# MG_0428.net
KiCad netlist of a schematic drawn in EasyEDA Pro
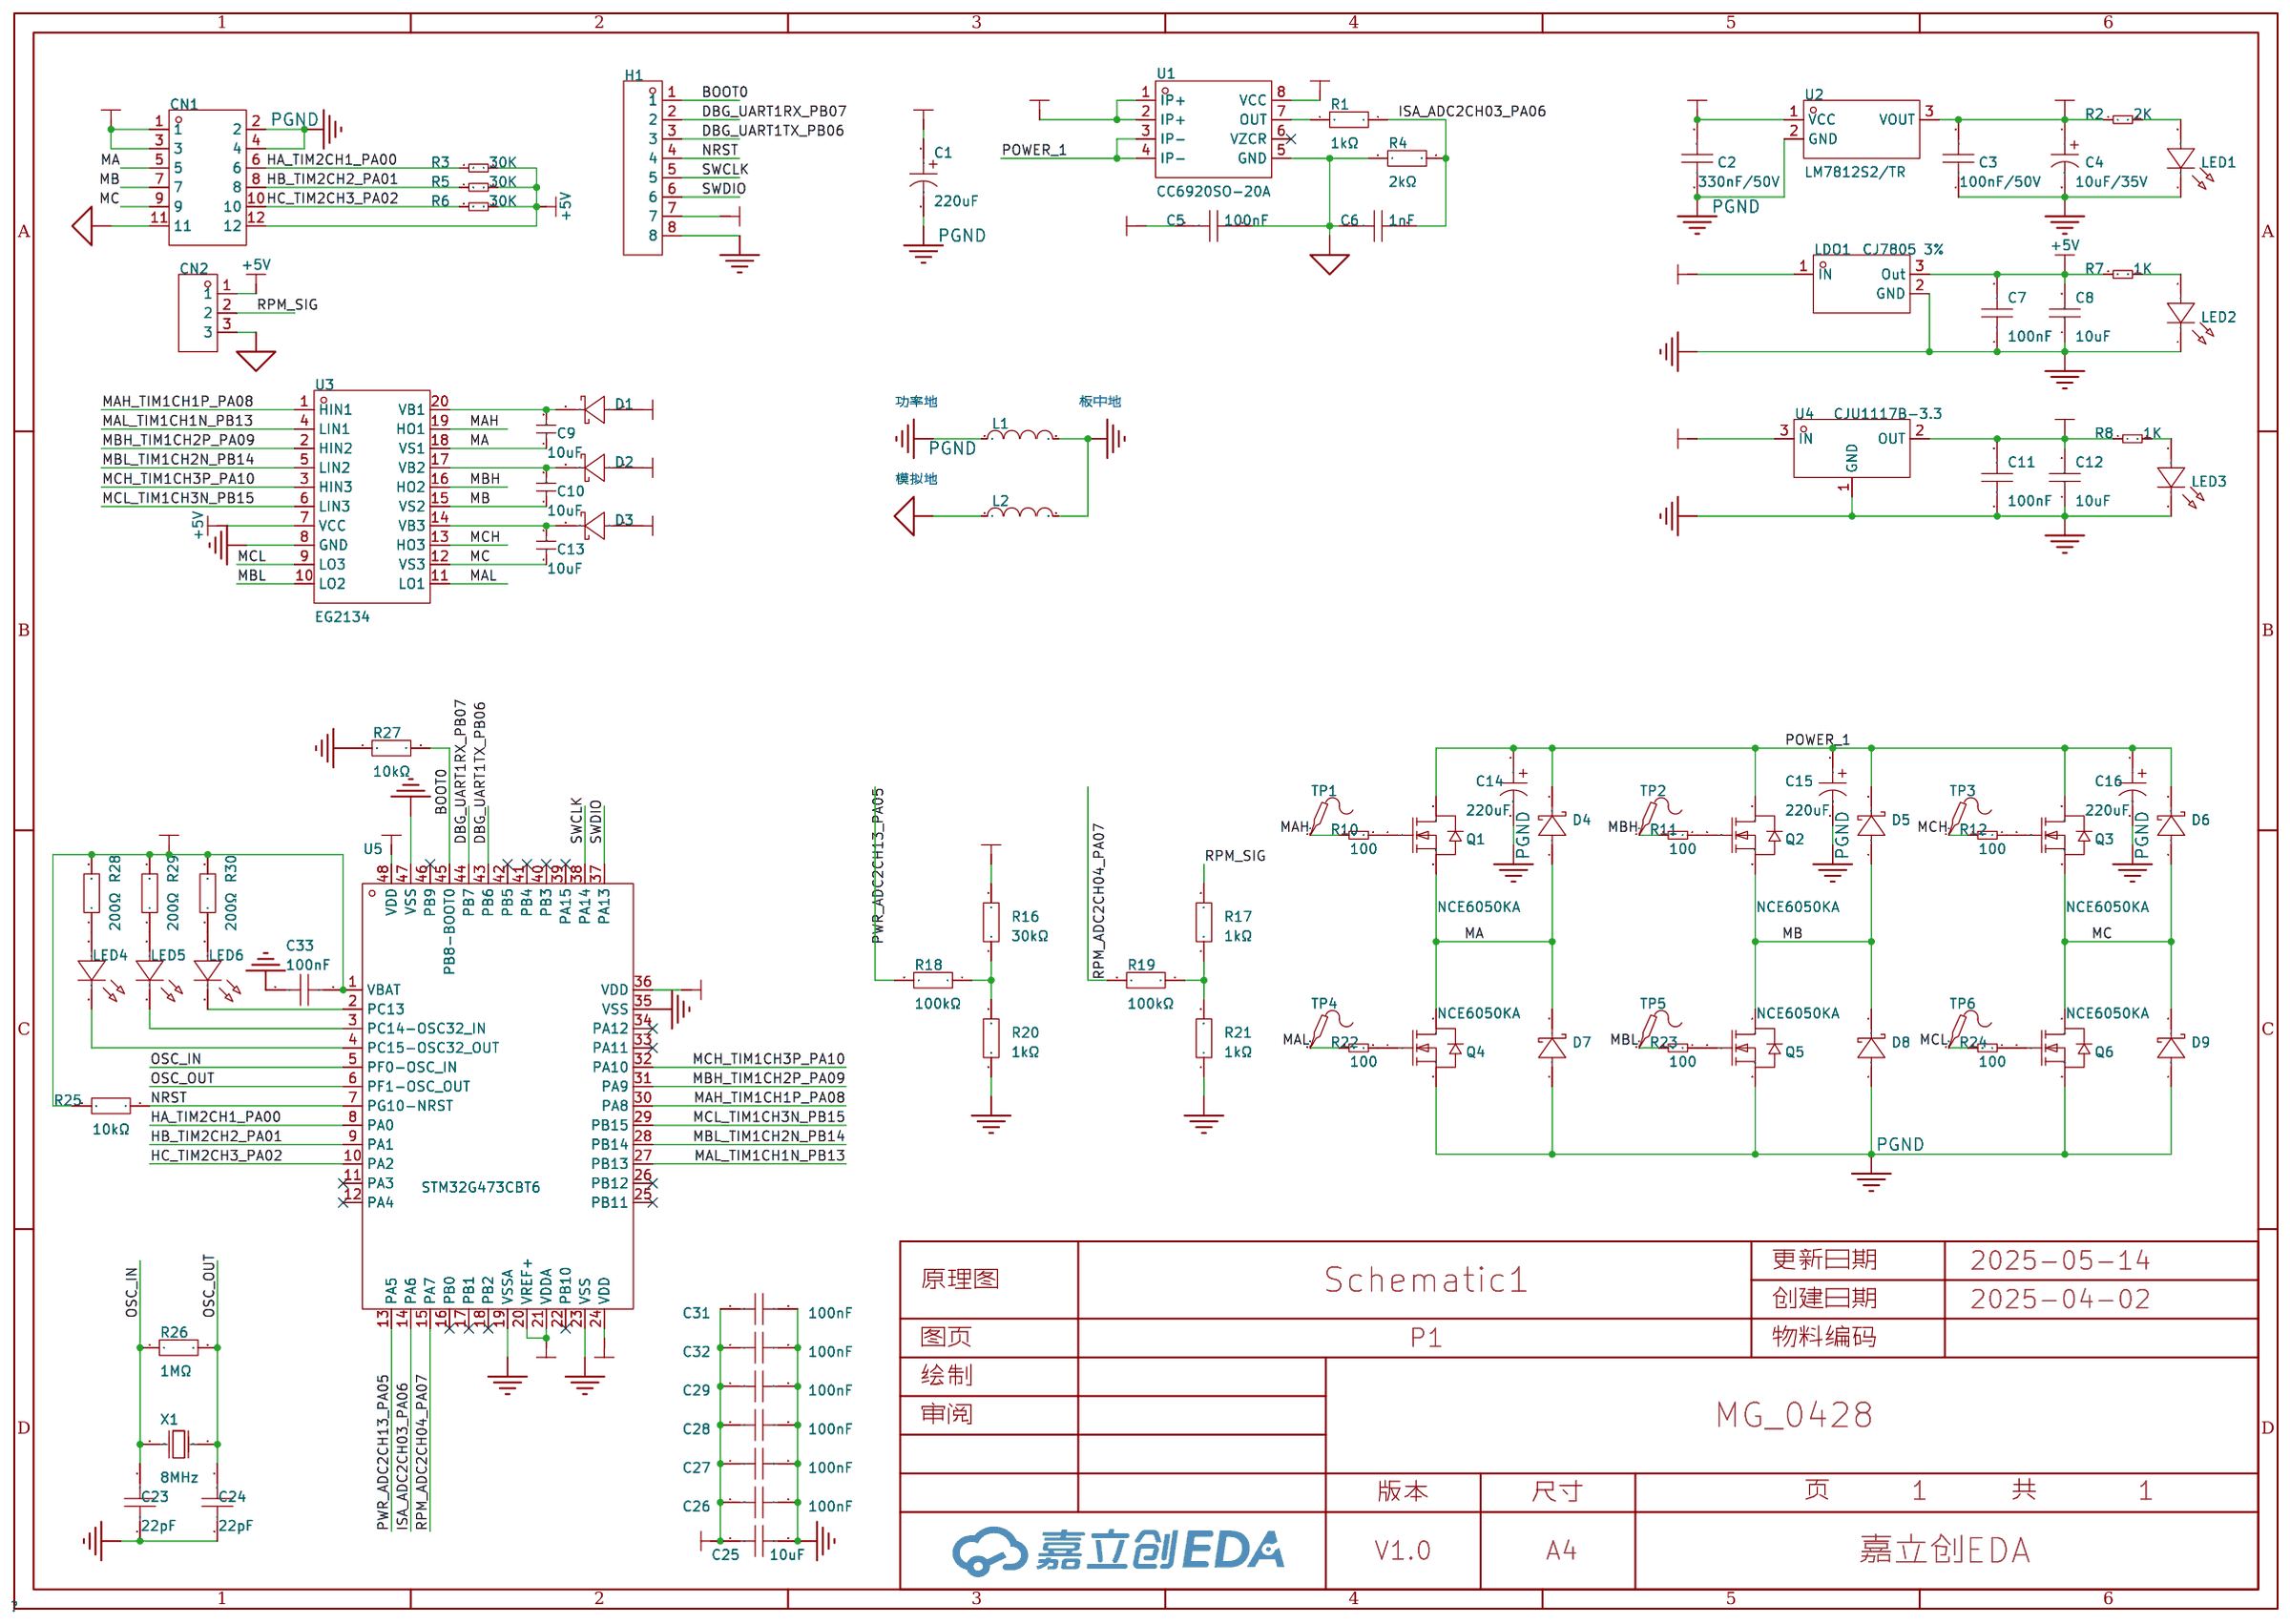
[diagram p0: schematic sheet]

(export (version "E")
  (design (tool "Eeschema 10.0.6"))
  (components
    (comp (ref "C1")
      (value "220uF")
      (footprint "easyedapro:CAP-SMD_BD10.0-L10.3-W10.3-LS11.0-FD")
      (description "容值:220uF;精度:±20%;额定电压:50V;纹波电流:230mA@120Hz;等效串联电阻:-;")
      (fields
        (field (name "Manufacturer Part") "RVT220UF50V67RV0021")
        (field (name "Manufacturer") "KNSCHA(科尼盛)")
      )
      (libsource (lib "easyedapro") (part "RVT220UF50V67RV0021"))
    )
    (comp (ref "C2")
      (value "330nF/50V")
      (footprint "easyedapro:C0603")
      (description "容值:330nF;精度:±10%;额定电压:50V;材质(温度系数):X7R;")
      (fields
        (field (name "Manufacturer Part") "TCC0603X7R334K500CT")
        (field (name "Manufacturer") "CCTC(三环)")
      )
      (libsource (lib "easyedapro") (part "TCC0603X7R334K500CT"))
    )
    (comp (ref "C3")
      (value "100nF/50V")
      (footprint "easyedapro:C0603")
      (description "容值:100nF;精度:±10%;额定电压:50V;材质(温度系数):X7R;")
      (fields
        (field (name "Manufacturer Part") "CC0603KRX7R9BB104")
        (field (name "Manufacturer") "YAGEO(国巨)")
      )
      (libsource (lib "easyedapro") (part "CC0603KRX7R9BB104"))
    )
    (comp (ref "C4")
      (value "10uF/35V")
      (footprint "easyedapro:CAP-SMD_BD6.3-L6.6-W6.6-LS7.4-FD")
      (description "容值:220uF;精度:±20%;额定电压:25V;纹波电流:150mA@120Hz;等效串联电阻:-;")
      (fields (field (name "Manufacturer Part") "RVT1E221M0607") (field (name "Manufacturer") "ROQANG(容强)"))
      (libsource (lib "easyedapro") (part "RVT1E221M0607_C2918361"))
    )
    (comp (ref "C5")
      (value "100nF")
      (footprint "easyedapro:C0603")
      (description "容值:100nF;精度:±10%;额定电压:50V;材质(温度系数):X7R;")
      (fields
        (field (name "Manufacturer Part") "CC0603KRX7R9BB104")
        (field (name "Manufacturer") "YAGEO(国巨)")
      )
      (libsource (lib "easyedapro") (part "CC0603KRX7R9BB104"))
    )
    (comp (ref "C6")
      (value "1nF")
      (footprint "easyedapro:C0603")
      (description "容值:100nF;精度:±10%;额定电压:50V;材质(温度系数):X7R;")
      (fields
        (field (name "Manufacturer Part") "CC0603KRX7R9BB104")
        (field (name "Manufacturer") "YAGEO(国巨)")
      )
      (libsource (lib "easyedapro") (part "CC0603KRX7R9BB104"))
    )
    (comp (ref "C7")
      (value "100nF")
      (footprint "easyedapro:C0603")
      (description "容值:100nF;精度:±10%;额定电压:50V;材质(温度系数):X7R;")
      (fields
        (field (name "Manufacturer Part") "CC0603KRX7R9BB104")
        (field (name "Manufacturer") "YAGEO(国巨)")
      )
      (libsource (lib "easyedapro") (part "CC0603KRX7R9BB104"))
    )
    (comp (ref "C8")
      (value "10uF")
      (footprint "easyedapro:C1206")
      (description "容值:10uF;精度:±10%;额定电压:50V;材质(温度系数):X5R;")
      (fields
        (field (name "Manufacturer Part") "CL31A106KBHNNNE")
        (field (name "Manufacturer") "SAMSUNG(三星)")
      )
      (libsource (lib "easyedapro") (part "CL31A106KBHNNNE"))
    )
    (comp (ref "C9")
      (value "10uF")
      (footprint "easyedapro:C0603")
      (libsource (lib "easyedapro") (part "CapAcitance"))
    )
    (comp (ref "C10")
      (value "10uF")
      (footprint "easyedapro:C0603")
      (libsource (lib "easyedapro") (part "CapAcitance"))
    )
    (comp (ref "C11")
      (value "100nF")
      (footprint "easyedapro:C0603")
      (description "容值:100nF;精度:±10%;额定电压:50V;材质(温度系数):X7R;")
      (fields
        (field (name "Manufacturer Part") "CC0603KRX7R9BB104")
        (field (name "Manufacturer") "YAGEO(国巨)")
      )
      (libsource (lib "easyedapro") (part "CC0603KRX7R9BB104"))
    )
    (comp (ref "C12")
      (value "10uF")
      (footprint "easyedapro:C1206")
      (description "容值:10uF;精度:±10%;额定电压:50V;材质(温度系数):X5R;")
      (fields
        (field (name "Manufacturer Part") "CL31A106KBHNNNE")
        (field (name "Manufacturer") "SAMSUNG(三星)")
      )
      (libsource (lib "easyedapro") (part "CL31A106KBHNNNE"))
    )
    (comp (ref "C13")
      (value "10uF")
      (footprint "easyedapro:C0603")
      (libsource (lib "easyedapro") (part "CapAcitance"))
    )
    (comp (ref "C14")
      (value "220uF")
      (footprint "easyedapro:CAP-SMD_BD6.3-L6.6-W6.6-LS7.4-FD")
      (description "容值:220uF;精度:±20%;额定电压:25V;纹波电流:150mA@120Hz;等效串联电阻:-;")
      (fields (field (name "Manufacturer Part") "RVT1E221M0607") (field (name "Manufacturer") "ROQANG(容强)"))
      (libsource (lib "easyedapro") (part "RVT1E221M0607_C2918361"))
    )
    (comp (ref "C15")
      (value "220uF")
      (footprint "easyedapro:CAP-SMD_BD6.3-L6.6-W6.6-LS7.4-FD")
      (description "容值:220uF;精度:±20%;额定电压:25V;纹波电流:150mA@120Hz;等效串联电阻:-;")
      (fields (field (name "Manufacturer Part") "RVT1E221M0607") (field (name "Manufacturer") "ROQANG(容强)"))
      (libsource (lib "easyedapro") (part "RVT1E221M0607_C2918361"))
    )
    (comp (ref "C16")
      (value "220uF")
      (footprint "easyedapro:CAP-SMD_BD6.3-L6.6-W6.6-LS7.4-FD")
      (description "容值:220uF;精度:±20%;额定电压:25V;纹波电流:150mA@120Hz;等效串联电阻:-;")
      (fields (field (name "Manufacturer Part") "RVT1E221M0607") (field (name "Manufacturer") "ROQANG(容强)"))
      (libsource (lib "easyedapro") (part "RVT1E221M0607_C2918361"))
    )
    (comp (ref "C23")
      (value "22pF")
      (footprint "easyedapro:C0402")
      (description "容值:22pF;精度:±1%;额定电压:50V;材质(温度系数):NP0;")
      (fields
        (field (name "Manufacturer Part") "CC0402FRNPO9BN220")
        (field (name "Manufacturer") "YAGEO(国巨)")
      )
      (libsource (lib "easyedapro") (part "CC0402FRNPO9BN220"))
    )
    (comp (ref "C24")
      (value "22pF")
      (footprint "easyedapro:C0402")
      (description "容值:22pF;精度:±1%;额定电压:50V;材质(温度系数):NP0;")
      (fields
        (field (name "Manufacturer Part") "CC0402FRNPO9BN220")
        (field (name "Manufacturer") "YAGEO(国巨)")
      )
      (libsource (lib "easyedapro") (part "CC0402FRNPO9BN220"))
    )
    (comp (ref "C25")
      (value "10uF")
      (footprint "easyedapro:C0402")
      (description "容值:10uF;精度:±20%;额定电压:10V;材质(温度系数):X5R;")
      (fields
        (field (name "Manufacturer Part") "HGC0402R5106M100NTEJ")
        (field (name "Manufacturer") "Chinocera(华瓷)")
      )
      (libsource (lib "easyedapro") (part "HGC0402R5106M100NTEJ"))
    )
    (comp (ref "C26")
      (value "100nF")
      (footprint "easyedapro:C0402")
      (description "容值:100nF;精度:±10%;额定电压:50V;材质(温度系数):X7R;")
      (fields
        (field (name "Manufacturer Part") "CL05B104KB54PNC")
        (field (name "Manufacturer") "SAMSUNG(三星)")
      )
      (libsource (lib "easyedapro") (part "CL05B104KB54PNC"))
    )
    (comp (ref "C27")
      (value "100nF")
      (footprint "easyedapro:C0402")
      (description "容值:100nF;精度:±10%;额定电压:50V;材质(温度系数):X7R;")
      (fields
        (field (name "Manufacturer Part") "CL05B104KB54PNC")
        (field (name "Manufacturer") "SAMSUNG(三星)")
      )
      (libsource (lib "easyedapro") (part "CL05B104KB54PNC"))
    )
    (comp (ref "C28")
      (value "100nF")
      (footprint "easyedapro:C0402")
      (description "容值:100nF;精度:±10%;额定电压:50V;材质(温度系数):X7R;")
      (fields
        (field (name "Manufacturer Part") "CL05B104KB54PNC")
        (field (name "Manufacturer") "SAMSUNG(三星)")
      )
      (libsource (lib "easyedapro") (part "CL05B104KB54PNC"))
    )
    (comp (ref "C29")
      (value "100nF")
      (footprint "easyedapro:C0402")
      (description "容值:100nF;精度:±10%;额定电压:50V;材质(温度系数):X7R;")
      (fields
        (field (name "Manufacturer Part") "CL05B104KB54PNC")
        (field (name "Manufacturer") "SAMSUNG(三星)")
      )
      (libsource (lib "easyedapro") (part "CL05B104KB54PNC"))
    )
    (comp (ref "C31")
      (value "100nF")
      (footprint "easyedapro:C0402")
      (description "容值:100nF;精度:±10%;额定电压:50V;材质(温度系数):X7R;")
      (fields
        (field (name "Manufacturer Part") "CL05B104KB54PNC")
        (field (name "Manufacturer") "SAMSUNG(三星)")
      )
      (libsource (lib "easyedapro") (part "CL05B104KB54PNC"))
    )
    (comp (ref "C32")
      (value "100nF")
      (footprint "easyedapro:C0402")
      (description "容值:100nF;精度:±10%;额定电压:50V;材质(温度系数):X7R;")
      (fields
        (field (name "Manufacturer Part") "CL05B104KB54PNC")
        (field (name "Manufacturer") "SAMSUNG(三星)")
      )
      (libsource (lib "easyedapro") (part "CL05B104KB54PNC"))
    )
    (comp (ref "C33")
      (value "100nF")
      (footprint "easyedapro:C0402")
      (description "容值:100nF;精度:±10%;额定电压:50V;材质(温度系数):X7R;")
      (fields
        (field (name "Manufacturer Part") "CL05B104KB54PNC")
        (field (name "Manufacturer") "SAMSUNG(三星)")
      )
      (libsource (lib "easyedapro") (part "CL05B104KB54PNC"))
    )
    (comp (ref "CN1")
      (value "HC-MX3.0-2*6A")
      (footprint "easyedapro:CONN-TH_12P-P3.00_HC-MX3.0-2X6A")
      (fields (field (name "Manufacturer") "HCTL(华灿天禄)"))
      (libsource (lib "easyedapro") (part "HC-MX3.0-2*6A"))
    )
    (comp (ref "CN2")
      (value "ZX-XH2.54-3PZZ")
      (footprint "easyedapro:CONN-TH_3P-P2.54_2501S-3P")
      (fields (field (name "Manufacturer") "Megastar(兆星)"))
      (libsource (lib "easyedapro") (part "ZX-XH2.54-3PZZ"))
    )
    (comp (ref "D1")
      (value "BAT46W")
      (footprint "easyedapro:SOD-123_L2.7-W1.6-LS3.7-FD")
      (description "二极管配置:独立式;正向压降(Vf):450mV@10mA;直流反向耐压(Vr):100V;整流电流:150mA;")
      (fields (field (name "Manufacturer") "宏迦橙"))
      (libsource (lib "easyedapro") (part "BAT46W_C7420332"))
    )
    (comp (ref "D2")
      (value "BAT46W")
      (footprint "easyedapro:SOD-123_L2.7-W1.6-LS3.7-FD")
      (description "二极管配置:独立式;正向压降(Vf):450mV@10mA;直流反向耐压(Vr):100V;整流电流:150mA;")
      (fields (field (name "Manufacturer") "宏迦橙"))
      (libsource (lib "easyedapro") (part "BAT46W_C7420332"))
    )
    (comp (ref "D3")
      (value "BAT46W")
      (footprint "easyedapro:SOD-123_L2.7-W1.6-LS3.7-FD")
      (description "二极管配置:独立式;正向压降(Vf):450mV@10mA;直流反向耐压(Vr):100V;整流电流:150mA;")
      (fields (field (name "Manufacturer") "宏迦橙"))
      (libsource (lib "easyedapro") (part "BAT46W_C7420332"))
    )
    (comp (ref "D4")
      (value "BAT46W")
      (footprint "easyedapro:SOD-123_L2.7-W1.6-LS3.7-FD")
      (description "二极管配置:独立式;正向压降(Vf):450mV@10mA;直流反向耐压(Vr):100V;整流电流:150mA;")
      (fields (field (name "Manufacturer") "宏迦橙"))
      (libsource (lib "easyedapro") (part "BAT46W_C7420332"))
    )
    (comp (ref "D5")
      (value "BAT46W")
      (footprint "easyedapro:SOD-123_L2.7-W1.6-LS3.7-FD")
      (description "二极管配置:独立式;正向压降(Vf):450mV@10mA;直流反向耐压(Vr):100V;整流电流:150mA;")
      (fields (field (name "Manufacturer") "宏迦橙"))
      (libsource (lib "easyedapro") (part "BAT46W_C7420332"))
    )
    (comp (ref "D6")
      (value "BAT46W")
      (footprint "easyedapro:SOD-123_L2.7-W1.6-LS3.7-FD")
      (description "二极管配置:独立式;正向压降(Vf):450mV@10mA;直流反向耐压(Vr):100V;整流电流:150mA;")
      (fields (field (name "Manufacturer") "宏迦橙"))
      (libsource (lib "easyedapro") (part "BAT46W_C7420332"))
    )
    (comp (ref "D7")
      (value "BAT46W")
      (footprint "easyedapro:SOD-123_L2.7-W1.6-LS3.7-FD")
      (description "二极管配置:独立式;正向压降(Vf):450mV@10mA;直流反向耐压(Vr):100V;整流电流:150mA;")
      (fields (field (name "Manufacturer") "宏迦橙"))
      (libsource (lib "easyedapro") (part "BAT46W_C7420332"))
    )
    (comp (ref "D8")
      (value "BAT46W")
      (footprint "easyedapro:SOD-123_L2.7-W1.6-LS3.7-FD")
      (description "二极管配置:独立式;正向压降(Vf):450mV@10mA;直流反向耐压(Vr):100V;整流电流:150mA;")
      (fields (field (name "Manufacturer") "宏迦橙"))
      (libsource (lib "easyedapro") (part "BAT46W_C7420332"))
    )
    (comp (ref "D9")
      (value "BAT46W")
      (footprint "easyedapro:SOD-123_L2.7-W1.6-LS3.7-FD")
      (description "二极管配置:独立式;正向压降(Vf):450mV@10mA;直流反向耐压(Vr):100V;整流电流:150mA;")
      (fields (field (name "Manufacturer") "宏迦橙"))
      (libsource (lib "easyedapro") (part "BAT46W_C7420332"))
    )
    (comp (ref "H1")
      (value "PZ254V-11-08P")
      (footprint "easyedapro:HDR-TH_8P-P2.54-V-M")
      (fields (field (name "Manufacturer") "XFCN(兴飞)"))
      (libsource (lib "easyedapro") (part "PZ254V-11-08P"))
    )
    (comp (ref "L1")
      (value "CBM201209U300T")
      (footprint "easyedapro:L0805")
      (description "标称阻抗@测试频率:30Ω@100MHz;误差:±25%;直流电阻(RDC):10mΩ;")
      (fields (field (name "Manufacturer") "FH(风华)"))
      (libsource (lib "easyedapro") (part "CBM201209U300T"))
    )
    (comp (ref "L2")
      (value "CBM201209U300T")
      (footprint "easyedapro:L0805")
      (description "标称阻抗@测试频率:30Ω@100MHz;误差:±25%;直流电阻(RDC):10mΩ;")
      (fields (field (name "Manufacturer") "FH(风华)"))
      (libsource (lib "easyedapro") (part "CBM201209U300T"))
    )
    (comp (ref "LDO1")
      (value "CJ7805 3%")
      (footprint "easyedapro:TO-252-2_L6.6-W6.1-P4.58-LS10.1-BR-CW")
      (description "输出类型:固定;最大输入电压:35V;输出电压:5V;最大输出电流:1.5A;输出极性:正极;")
      (fields (field (name "Manufacturer") "CJ(江苏长电/长晶)"))
      (libsource (lib "easyedapro") (part "CJ7805 3%"))
    )
    (comp (ref "LED1")
      (value "XL-1608SURC-06")
      (footprint "easyedapro:LED0603-RD_RED")
      (description "发光颜色:红色;功率:55mW;正向电流:25mA;主波长:617nm~621nm;透镜颜色:无色透明透镜;色温:-;发光角度:120°;载带方式:正贴;工作温度:-30°C~+85°C;")
      (fields (field (name "Manufacturer") "XINGLIGHT(成兴光)"))
      (libsource (lib "easyedapro") (part "XL-1608SURC-06"))
    )
    (comp (ref "LED2")
      (value "XL-1608SURC-06")
      (footprint "easyedapro:LED0603-RD_RED")
      (description "发光颜色:红色;功率:55mW;正向电流:25mA;主波长:617nm~621nm;透镜颜色:无色透明透镜;色温:-;发光角度:120°;载带方式:正贴;工作温度:-30°C~+85°C;")
      (fields (field (name "Manufacturer") "XINGLIGHT(成兴光)"))
      (libsource (lib "easyedapro") (part "XL-1608SURC-06"))
    )
    (comp (ref "LED3")
      (value "XL-1608SURC-06")
      (footprint "easyedapro:LED0603-RD_RED")
      (description "发光颜色:红色;功率:55mW;正向电流:25mA;主波长:617nm~621nm;透镜颜色:无色透明透镜;色温:-;发光角度:120°;载带方式:正贴;工作温度:-30°C~+85°C;")
      (fields (field (name "Manufacturer") "XINGLIGHT(成兴光)"))
      (libsource (lib "easyedapro") (part "XL-1608SURC-06"))
    )
    (comp (ref "LED4")
      (value "XL-1608SURC-06")
      (footprint "easyedapro:LED0603-RD_RED")
      (description "发光颜色:红色;功率:55mW;正向电流:25mA;主波长:617nm~621nm;透镜颜色:无色透明透镜;色温:-;发光角度:120°;载带方式:正贴;工作温度:-30°C~+85°C;")
      (fields (field (name "Manufacturer") "XINGLIGHT(成兴光)"))
      (libsource (lib "easyedapro") (part "XL-1608SURC-06"))
    )
    (comp (ref "LED5")
      (value "XL-1608SURC-06")
      (footprint "easyedapro:LED0603-RD_RED")
      (description "发光颜色:红色;功率:55mW;正向电流:25mA;主波长:617nm~621nm;透镜颜色:无色透明透镜;色温:-;发光角度:120°;载带方式:正贴;工作温度:-30°C~+85°C;")
      (fields (field (name "Manufacturer") "XINGLIGHT(成兴光)"))
      (libsource (lib "easyedapro") (part "XL-1608SURC-06"))
    )
    (comp (ref "LED6")
      (value "XL-1608SURC-06")
      (footprint "easyedapro:LED0603-RD_RED")
      (description "发光颜色:红色;功率:55mW;正向电流:25mA;主波长:617nm~621nm;透镜颜色:无色透明透镜;色温:-;发光角度:120°;载带方式:正贴;工作温度:-30°C~+85°C;")
      (fields (field (name "Manufacturer") "XINGLIGHT(成兴光)"))
      (libsource (lib "easyedapro") (part "XL-1608SURC-06"))
    )
    (comp (ref "Q1")
      (value "NCE6050KA")
      (footprint "easyedapro:TO-252-2_L6.6-W6.1-P4.57-LS10.1-TL-CW")
      (fields (field (name "Manufacturer") "NCE(无锡新洁能)"))
      (libsource (lib "easyedapro") (part "NCE6050KA"))
    )
    (comp (ref "Q2")
      (value "NCE6050KA")
      (footprint "easyedapro:TO-252-2_L6.6-W6.1-P4.57-LS10.1-TL-CW")
      (fields (field (name "Manufacturer") "NCE(无锡新洁能)"))
      (libsource (lib "easyedapro") (part "NCE6050KA"))
    )
    (comp (ref "Q3")
      (value "NCE6050KA")
      (footprint "easyedapro:TO-252-2_L6.6-W6.1-P4.57-LS10.1-TL-CW")
      (fields (field (name "Manufacturer") "NCE(无锡新洁能)"))
      (libsource (lib "easyedapro") (part "NCE6050KA"))
    )
    (comp (ref "Q4")
      (value "NCE6050KA")
      (footprint "easyedapro:TO-252-2_L6.6-W6.1-P4.57-LS10.1-TL-CW")
      (fields (field (name "Manufacturer") "NCE(无锡新洁能)"))
      (libsource (lib "easyedapro") (part "NCE6050KA"))
    )
    (comp (ref "Q5")
      (value "NCE6050KA")
      (footprint "easyedapro:TO-252-2_L6.6-W6.1-P4.57-LS10.1-TL-CW")
      (fields (field (name "Manufacturer") "NCE(无锡新洁能)"))
      (libsource (lib "easyedapro") (part "NCE6050KA"))
    )
    (comp (ref "Q6")
      (value "NCE6050KA")
      (footprint "easyedapro:TO-252-2_L6.6-W6.1-P4.57-LS10.1-TL-CW")
      (fields (field (name "Manufacturer") "NCE(无锡新洁能)"))
      (libsource (lib "easyedapro") (part "NCE6050KA"))
    )
    (comp (ref "R1")
      (value "1kΩ")
      (footprint "easyedapro:R0603")
      (description "电阻类型:厚膜电阻;阻值:10kΩ;精度:±1%;功率:100mW;最大工作电压:75V;温度系数:±100ppm/°C;")
      (fields
        (field (name "Manufacturer Part") "0603WAF1002T5E")
        (field (name "Manufacturer") "UNI-ROYAL(厚声)")
      )
      (libsource (lib "easyedapro") (part "0603WAF1002T5E"))
    )
    (comp (ref "R2") (value "2K") (footprint "easyedapro:R0603") (libsource (lib "easyedapro") (part "电阻")))
    (comp (ref "R3") (value "30K") (footprint "easyedapro:R0603") (libsource (lib "easyedapro") (part "电阻")))
    (comp (ref "R4")
      (value "2kΩ")
      (footprint "easyedapro:R0603")
      (description "电阻类型:厚膜电阻;阻值:10kΩ;精度:±1%;功率:100mW;最大工作电压:75V;温度系数:±100ppm/°C;")
      (fields
        (field (name "Manufacturer Part") "0603WAF1002T5E")
        (field (name "Manufacturer") "UNI-ROYAL(厚声)")
      )
      (libsource (lib "easyedapro") (part "0603WAF1002T5E"))
    )
    (comp (ref "R5") (value "30K") (footprint "easyedapro:R0603") (libsource (lib "easyedapro") (part "电阻")))
    (comp (ref "R6") (value "30K") (footprint "easyedapro:R0603") (libsource (lib "easyedapro") (part "电阻")))
    (comp (ref "R7") (value "1K") (footprint "easyedapro:R0603") (libsource (lib "easyedapro") (part "电阻")))
    (comp (ref "R8") (value "1K") (footprint "easyedapro:R0603") (libsource (lib "easyedapro") (part "电阻")))
    (comp (ref "R10") (value "100") (footprint "easyedapro:R0603") (libsource (lib "easyedapro") (part "电阻")))
    (comp (ref "R11") (value "100") (footprint "easyedapro:R0603") (libsource (lib "easyedapro") (part "电阻")))
    (comp (ref "R12") (value "100") (footprint "easyedapro:R0603") (libsource (lib "easyedapro") (part "电阻")))
    (comp (ref "R16")
      (value "30kΩ")
      (footprint "easyedapro:R0603")
      (description "电阻类型:厚膜电阻;阻值:10kΩ;精度:±1%;功率:100mW;最大工作电压:75V;温度系数:±100ppm/°C;")
      (fields
        (field (name "Manufacturer Part") "0603WAF1002T5E")
        (field (name "Manufacturer") "UNI-ROYAL(厚声)")
      )
      (libsource (lib "easyedapro") (part "0603WAF1002T5E"))
    )
    (comp (ref "R17")
      (value "1kΩ")
      (footprint "easyedapro:R0603")
      (description "电阻类型:厚膜电阻;阻值:10kΩ;精度:±1%;功率:100mW;最大工作电压:75V;温度系数:±100ppm/°C;")
      (fields
        (field (name "Manufacturer Part") "0603WAF1002T5E")
        (field (name "Manufacturer") "UNI-ROYAL(厚声)")
      )
      (libsource (lib "easyedapro") (part "0603WAF1002T5E"))
    )
    (comp (ref "R18")
      (value "100kΩ")
      (footprint "easyedapro:R0603")
      (description "电阻类型:厚膜电阻;阻值:10kΩ;精度:±1%;功率:100mW;最大工作电压:75V;温度系数:±100ppm/°C;")
      (fields
        (field (name "Manufacturer Part") "0603WAF1002T5E")
        (field (name "Manufacturer") "UNI-ROYAL(厚声)")
      )
      (libsource (lib "easyedapro") (part "0603WAF1002T5E"))
    )
    (comp (ref "R19")
      (value "100kΩ")
      (footprint "easyedapro:R0603")
      (description "电阻类型:厚膜电阻;阻值:10kΩ;精度:±1%;功率:100mW;最大工作电压:75V;温度系数:±100ppm/°C;")
      (fields
        (field (name "Manufacturer Part") "0603WAF1002T5E")
        (field (name "Manufacturer") "UNI-ROYAL(厚声)")
      )
      (libsource (lib "easyedapro") (part "0603WAF1002T5E"))
    )
    (comp (ref "R20")
      (value "1kΩ")
      (footprint "easyedapro:R0603")
      (description "电阻类型:厚膜电阻;阻值:10kΩ;精度:±1%;功率:100mW;最大工作电压:75V;温度系数:±100ppm/°C;")
      (fields
        (field (name "Manufacturer Part") "0603WAF1002T5E")
        (field (name "Manufacturer") "UNI-ROYAL(厚声)")
      )
      (libsource (lib "easyedapro") (part "0603WAF1002T5E"))
    )
    (comp (ref "R21")
      (value "1kΩ")
      (footprint "easyedapro:R0603")
      (description "电阻类型:厚膜电阻;阻值:10kΩ;精度:±1%;功率:100mW;最大工作电压:75V;温度系数:±100ppm/°C;")
      (fields
        (field (name "Manufacturer Part") "0603WAF1002T5E")
        (field (name "Manufacturer") "UNI-ROYAL(厚声)")
      )
      (libsource (lib "easyedapro") (part "0603WAF1002T5E"))
    )
    (comp (ref "R22") (value "100") (footprint "easyedapro:R0603") (libsource (lib "easyedapro") (part "电阻")))
    (comp (ref "R23") (value "100") (footprint "easyedapro:R0603") (libsource (lib "easyedapro") (part "电阻")))
    (comp (ref "R24") (value "100") (footprint "easyedapro:R0603") (libsource (lib "easyedapro") (part "电阻")))
    (comp (ref "R25")
      (value "10kΩ")
      (footprint "easyedapro:R0603")
      (description "电阻类型:厚膜电阻;阻值:10kΩ;精度:±1%;功率:100mW;最大工作电压:75V;温度系数:±100ppm/°C;")
      (fields
        (field (name "Manufacturer Part") "0603WAF1002T5E")
        (field (name "Manufacturer") "UNI-ROYAL(厚声)")
      )
      (libsource (lib "easyedapro") (part "0603WAF1002T5E"))
    )
    (comp (ref "R26")
      (value "1MΩ")
      (footprint "easyedapro:R0402")
      (description "电阻类型:厚膜电阻;阻值:1MΩ;精度:±1%;功率:62.5mW;最大工作电压:50V;温度系数:±100ppm/°C;")
      (fields
        (field (name "Manufacturer Part") "0402WGF1004TCE")
        (field (name "Manufacturer") "UNI-ROYAL(厚声)")
      )
      (libsource (lib "easyedapro") (part "0402WGF1004TCE"))
    )
    (comp (ref "R27")
      (value "10kΩ")
      (footprint "easyedapro:R0402")
      (description "电阻类型:厚膜电阻;阻值:10kΩ;精度:±1%;功率:62.5mW;最大工作电压:50V;温度系数:±100ppm/°C;")
      (fields
        (field (name "Manufacturer Part") "0402WGF1002TCE")
        (field (name "Manufacturer") "UNI-ROYAL(厚声)")
      )
      (libsource (lib "easyedapro") (part "0402WGF1002TCE"))
    )
    (comp (ref "R28")
      (value "200Ω")
      (footprint "easyedapro:R0402")
      (description "电阻类型:厚膜电阻;阻值:200Ω;精度:±1%;功率:62.5mW;最大工作电压:50V;温度系数:±100ppm/°C;")
      (fields
        (field (name "Manufacturer Part") "0402WGF2000TCE")
        (field (name "Manufacturer") "UNI-ROYAL(厚声)")
      )
      (libsource (lib "easyedapro") (part "0402WGF2000TCE"))
    )
    (comp (ref "R29")
      (value "200Ω")
      (footprint "easyedapro:R0402")
      (description "电阻类型:厚膜电阻;阻值:200Ω;精度:±1%;功率:62.5mW;最大工作电压:50V;温度系数:±100ppm/°C;")
      (fields
        (field (name "Manufacturer Part") "0402WGF2000TCE")
        (field (name "Manufacturer") "UNI-ROYAL(厚声)")
      )
      (libsource (lib "easyedapro") (part "0402WGF2000TCE"))
    )
    (comp (ref "R30")
      (value "200Ω")
      (footprint "easyedapro:R0402")
      (description "电阻类型:厚膜电阻;阻值:200Ω;精度:±1%;功率:62.5mW;最大工作电压:50V;温度系数:±100ppm/°C;")
      (fields
        (field (name "Manufacturer Part") "0402WGF2000TCE")
        (field (name "Manufacturer") "UNI-ROYAL(厚声)")
      )
      (libsource (lib "easyedapro") (part "0402WGF2000TCE"))
    )
    (comp (ref "TP1")
      (value "~")
      (footprint "easyedapro:testpoint-smd_bd1.5_p70-5000045r")
      (description "Test Point 测试点")
      (libsource (lib "easyedapro") (part "Test-Point"))
    )
    (comp (ref "TP2")
      (value "~")
      (footprint "easyedapro:testpoint-smd_bd1.5_p70-5000045r")
      (description "Test Point 测试点")
      (libsource (lib "easyedapro") (part "Test-Point"))
    )
    (comp (ref "TP3")
      (value "~")
      (footprint "easyedapro:testpoint-smd_bd1.5_p70-5000045r")
      (description "Test Point 测试点")
      (libsource (lib "easyedapro") (part "Test-Point"))
    )
    (comp (ref "TP4")
      (value "~")
      (footprint "easyedapro:testpoint-smd_bd1.5_p70-5000045r")
      (description "Test Point 测试点")
      (libsource (lib "easyedapro") (part "Test-Point"))
    )
    (comp (ref "TP5")
      (value "~")
      (footprint "easyedapro:testpoint-smd_bd1.5_p70-5000045r")
      (description "Test Point 测试点")
      (libsource (lib "easyedapro") (part "Test-Point"))
    )
    (comp (ref "TP6")
      (value "~")
      (footprint "easyedapro:testpoint-smd_bd1.5_p70-5000045r")
      (description "Test Point 测试点")
      (libsource (lib "easyedapro") (part "Test-Point"))
    )
    (comp (ref "U1")
      (value "CC6920SO-20A")
      (footprint "easyedapro:SOP-8_L5.0-W4.0-P1.27-LS6.2-BL")
      (fields (field (name "Manufacturer") "CrossChip(成都芯进)"))
      (libsource (lib "easyedapro") (part "CC6920SO-20A"))
    )
    (comp (ref "U2")
      (value "LM7812S2/TR")
      (footprint "easyedapro:TO-263-2_L10.2-W8.7-P5.08-LS15.1-BL")
      (description "线性稳压器(LDO)   固定电压稳压器")
      (fields (field (name "Manufacturer") "HGSEMI(华冠)"))
      (libsource (lib "easyedapro") (part "LM7812S2/TR"))
    )
    (comp (ref "U3")
      (value "EG2134")
      (footprint "easyedapro:TSSOP-20_L6.5-W4.4-P0.65-LS6.4-BL")
      (fields (field (name "Manufacturer") "EG(屹晶微)"))
      (libsource (lib "easyedapro") (part "EG2134_C480661"))
    )
    (comp (ref "U4")
      (value "CJU1117B-3.3")
      (footprint "easyedapro:TO-252-2_L6.6-W6.1-P4.57-LS9.9-TL-CW")
      (description "最大输入电压:20V;输出电压:3.3V;最大输出电流:1A;电源纹波抑制比(PSRR):65dB;")
      (fields (field (name "Manufacturer") "CJ(江苏长电/长晶)"))
      (libsource (lib "easyedapro") (part "CJU1117B-3.3"))
    )
    (comp (ref "U5")
      (value "STM32G473CBT6")
      (footprint "easyedapro:LQFP-48_L7.0-W7.0-P0.50-LS9.0-BL")
      (fields (field (name "Manufacturer") "ST(意法半导体)"))
      (libsource (lib "easyedapro") (part "STM32G473CBT6"))
    )
    (comp (ref "X1")
      (value "8MHz")
      (footprint "easyedapro:CRYSTAL-SMD_L5.0-W3.2")
      (description "晶振类型:贴片晶振;频率:8MHz;常温频差:±10ppm;外接负载电容:20pF;频率稳定度(全温):±20ppm;")
      (fields (field (name "Manufacturer Part") "X50328MSB2GI") (field (name "Manufacturer") "YXC(扬兴晶振)"))
      (libsource (lib "easyedapro") (part "X50328MSB2GI"))
    )
  )
  (nets
    (net (code "1") (name "+5V") (class "Default")
      (node (ref "C5") (pin "2") (pinfunction "2_2") (pintype "unspecified"))
      (node (ref "C7") (pin "2") (pinfunction "2_2") (pintype "unspecified"))
      (node (ref "C8") (pin "2") (pinfunction "2_2") (pintype "input"))
      (node (ref "CN1") (pin "12") (pinfunction "12_12") (pintype "unspecified"))
      (node (ref "CN2") (pin "1") (pinfunction "1_1") (pintype "unspecified"))
      (node (ref "LDO1") (pin "3") (pinfunction "Out_3") (pintype "unspecified"))
      (node (ref "R3") (pin "1") (pinfunction "1_1") (pintype "input"))
      (node (ref "R5") (pin "1") (pinfunction "1_1") (pintype "input"))
      (node (ref "R6") (pin "1") (pinfunction "1_1") (pintype "input"))
      (node (ref "R7") (pin "1") (pinfunction "1_1") (pintype "input"))
      (node (ref "U1") (pin "8") (pinfunction "VCC_8") (pintype "input"))
      (node (ref "U3") (pin "7") (pinfunction "VCC_7") (pintype "unspecified"))
    )
    (net (code "2") (name "/BOOT0") (class "Default")
      (node (ref "H1") (pin "1") (pinfunction "1_1") (pintype "unspecified"))
      (node (ref "R27") (pin "2") (pinfunction "2_2") (pintype "input"))
      (node (ref "U5") (pin "45") (pinfunction "PB8-BOOT0_45") (pintype "unspecified"))
    )
    (net (code "3") (name "/DBG_UART1RX_PB07") (class "Default")
      (node (ref "H1") (pin "2") (pinfunction "2_2") (pintype "unspecified"))
      (node (ref "U5") (pin "44") (pinfunction "PB7_44") (pintype "unspecified"))
    )
    (net (code "4") (name "/DBG_UART1TX_PB06") (class "Default")
      (node (ref "H1") (pin "3") (pinfunction "3_3") (pintype "unspecified"))
      (node (ref "U5") (pin "43") (pinfunction "PB6_43") (pintype "unspecified"))
    )
    (net (code "5") (name "/HA_TIM2CH1_PA00") (class "Default")
      (node (ref "CN1") (pin "6") (pinfunction "6_6") (pintype "unspecified"))
      (node (ref "R3") (pin "2") (pinfunction "2_2") (pintype "input"))
      (node (ref "U5") (pin "8") (pinfunction "PA0_8") (pintype "unspecified"))
    )
    (net (code "6") (name "/HB_TIM2CH2_PA01") (class "Default")
      (node (ref "CN1") (pin "8") (pinfunction "8_8") (pintype "unspecified"))
      (node (ref "R5") (pin "2") (pinfunction "2_2") (pintype "input"))
      (node (ref "U5") (pin "9") (pinfunction "PA1_9") (pintype "unspecified"))
    )
    (net (code "7") (name "/HC_TIM2CH3_PA02") (class "Default")
      (node (ref "CN1") (pin "10") (pinfunction "10_10") (pintype "unspecified"))
      (node (ref "R6") (pin "2") (pinfunction "2_2") (pintype "input"))
      (node (ref "U5") (pin "10") (pinfunction "PA2_10") (pintype "unspecified"))
    )
    (net (code "8") (name "/ISA_ADC2CH03_PA06") (class "Default")
      (node (ref "C6") (pin "2") (pinfunction "2_2") (pintype "unspecified"))
      (node (ref "R1") (pin "1") (pinfunction "1_1") (pintype "input"))
      (node (ref "R4") (pin "1") (pinfunction "1_1") (pintype "input"))
      (node (ref "U5") (pin "14") (pinfunction "PA6_14") (pintype "unspecified"))
    )
    (net (code "9") (name "/MA") (class "Default")
      (node (ref "C9") (pin "1") (pinfunction "1_1") (pintype "input"))
      (node (ref "CN1") (pin "5") (pinfunction "5_5") (pintype "unspecified"))
      (node (ref "D4") (pin "1") (pinfunction "A_1") (pintype "unspecified"))
      (node (ref "D7") (pin "2") (pinfunction "K_2") (pintype "unspecified"))
      (node (ref "Q1") (pin "3") (pinfunction "S_3") (pintype "unspecified"))
      (node (ref "Q4") (pin "2") (pinfunction "D_2") (pintype "unspecified"))
      (node (ref "U3") (pin "18") (pinfunction "VS1_18") (pintype "unspecified"))
    )
    (net (code "10") (name "/MAH") (class "Default")
      (node (ref "R10") (pin "2") (pinfunction "2_2") (pintype "input"))
      (node (ref "TP1") (pin "1") (pinfunction "1_1") (pintype "input"))
      (node (ref "U3") (pin "19") (pinfunction "HO1_19") (pintype "unspecified"))
    )
    (net (code "11") (name "/MAH_TIM1CH1P_PA08") (class "Default")
      (node (ref "U3") (pin "1") (pinfunction "HIN1_1") (pintype "unspecified"))
      (node (ref "U5") (pin "30") (pinfunction "PA8_30") (pintype "unspecified"))
    )
    (net (code "12") (name "/MAL") (class "Default")
      (node (ref "R22") (pin "2") (pinfunction "2_2") (pintype "input"))
      (node (ref "TP4") (pin "1") (pinfunction "1_1") (pintype "input"))
      (node (ref "U3") (pin "11") (pinfunction "LO1_11") (pintype "unspecified"))
    )
    (net (code "13") (name "/MAL_TIM1CH1N_PB13") (class "Default")
      (node (ref "U3") (pin "4") (pinfunction "LIN1_4") (pintype "unspecified"))
      (node (ref "U5") (pin "27") (pinfunction "PB13_27") (pintype "unspecified"))
    )
    (net (code "14") (name "/MB") (class "Default")
      (node (ref "C10") (pin "1") (pinfunction "1_1") (pintype "input"))
      (node (ref "CN1") (pin "7") (pinfunction "7_7") (pintype "unspecified"))
      (node (ref "D5") (pin "1") (pinfunction "A_1") (pintype "unspecified"))
      (node (ref "D8") (pin "2") (pinfunction "K_2") (pintype "unspecified"))
      (node (ref "Q2") (pin "3") (pinfunction "S_3") (pintype "unspecified"))
      (node (ref "Q5") (pin "2") (pinfunction "D_2") (pintype "unspecified"))
      (node (ref "U3") (pin "15") (pinfunction "VS2_15") (pintype "unspecified"))
    )
    (net (code "15") (name "/MBH") (class "Default")
      (node (ref "R11") (pin "2") (pinfunction "2_2") (pintype "input"))
      (node (ref "TP2") (pin "1") (pinfunction "1_1") (pintype "input"))
      (node (ref "U3") (pin "16") (pinfunction "HO2_16") (pintype "unspecified"))
    )
    (net (code "16") (name "/MBH_TIM1CH2P_PA09") (class "Default")
      (node (ref "U3") (pin "2") (pinfunction "HIN2_2") (pintype "unspecified"))
      (node (ref "U5") (pin "31") (pinfunction "PA9_31") (pintype "unspecified"))
    )
    (net (code "17") (name "/MBL") (class "Default")
      (node (ref "R23") (pin "2") (pinfunction "2_2") (pintype "input"))
      (node (ref "TP5") (pin "1") (pinfunction "1_1") (pintype "input"))
      (node (ref "U3") (pin "10") (pinfunction "LO2_10") (pintype "unspecified"))
    )
    (net (code "18") (name "/MBL_TIM1CH2N_PB14") (class "Default")
      (node (ref "U3") (pin "5") (pinfunction "LIN2_5") (pintype "unspecified"))
      (node (ref "U5") (pin "28") (pinfunction "PB14_28") (pintype "unspecified"))
    )
    (net (code "19") (name "/MC") (class "Default")
      (node (ref "C13") (pin "1") (pinfunction "1_1") (pintype "input"))
      (node (ref "CN1") (pin "9") (pinfunction "9_9") (pintype "unspecified"))
      (node (ref "D6") (pin "1") (pinfunction "A_1") (pintype "unspecified"))
      (node (ref "D9") (pin "2") (pinfunction "K_2") (pintype "unspecified"))
      (node (ref "Q3") (pin "3") (pinfunction "S_3") (pintype "unspecified"))
      (node (ref "Q6") (pin "2") (pinfunction "D_2") (pintype "unspecified"))
      (node (ref "U3") (pin "12") (pinfunction "VS3_12") (pintype "unspecified"))
    )
    (net (code "20") (name "/MCH") (class "Default")
      (node (ref "R12") (pin "2") (pinfunction "2_2") (pintype "input"))
      (node (ref "TP3") (pin "1") (pinfunction "1_1") (pintype "input"))
      (node (ref "U3") (pin "13") (pinfunction "HO3_13") (pintype "unspecified"))
    )
    (net (code "21") (name "/MCH_TIM1CH3P_PA10") (class "Default")
      (node (ref "U3") (pin "3") (pinfunction "HIN3_3") (pintype "unspecified"))
      (node (ref "U5") (pin "32") (pinfunction "PA10_32") (pintype "unspecified"))
    )
    (net (code "22") (name "/MCL") (class "Default")
      (node (ref "R24") (pin "2") (pinfunction "2_2") (pintype "input"))
      (node (ref "TP6") (pin "1") (pinfunction "1_1") (pintype "input"))
      (node (ref "U3") (pin "9") (pinfunction "LO3_9") (pintype "unspecified"))
    )
    (net (code "23") (name "/MCL_TIM1CH3N_PB15") (class "Default")
      (node (ref "U3") (pin "6") (pinfunction "LIN3_6") (pintype "unspecified"))
      (node (ref "U5") (pin "29") (pinfunction "PB15_29") (pintype "unspecified"))
    )
    (net (code "24") (name "/NRST") (class "Default")
      (node (ref "H1") (pin "4") (pinfunction "4_4") (pintype "unspecified"))
      (node (ref "R25") (pin "1") (pinfunction "1_1") (pintype "input"))
      (node (ref "U5") (pin "7") (pinfunction "PG10-NRST_7") (pintype "unspecified"))
    )
    (net (code "25") (name "/OSC_IN") (class "Default")
      (node (ref "C23") (pin "2") (pinfunction "2_2") (pintype "unspecified"))
      (node (ref "R26") (pin "1") (pinfunction "1_1") (pintype "input"))
      (node (ref "U5") (pin "5") (pinfunction "PF0-OSC_IN_5") (pintype "unspecified"))
      (node (ref "X1") (pin "2") (pinfunction "OSC2_2") (pintype "input"))
    )
    (net (code "26") (name "/OSC_OUT") (class "Default")
      (node (ref "C24") (pin "2") (pinfunction "2_2") (pintype "unspecified"))
      (node (ref "R26") (pin "2") (pinfunction "2_2") (pintype "input"))
      (node (ref "U5") (pin "6") (pinfunction "PF1-OSC_OUT_6") (pintype "unspecified"))
      (node (ref "X1") (pin "1") (pinfunction "OSC1_1") (pintype "input"))
    )
    (net (code "27") (name "/POWER_1") (class "Default")
      (node (ref "C14") (pin "1") (pinfunction "1_1") (pintype "input"))
      (node (ref "C15") (pin "1") (pinfunction "1_1") (pintype "input"))
      (node (ref "C16") (pin "1") (pinfunction "1_1") (pintype "input"))
      (node (ref "D4") (pin "2") (pinfunction "K_2") (pintype "unspecified"))
      (node (ref "D5") (pin "2") (pinfunction "K_2") (pintype "unspecified"))
      (node (ref "D6") (pin "2") (pinfunction "K_2") (pintype "unspecified"))
      (node (ref "Q1") (pin "2") (pinfunction "D_2") (pintype "unspecified"))
      (node (ref "Q2") (pin "2") (pinfunction "D_2") (pintype "unspecified"))
      (node (ref "Q3") (pin "2") (pinfunction "D_2") (pintype "unspecified"))
      (node (ref "U1") (pin "3") (pinfunction "IP-_3") (pintype "input"))
      (node (ref "U1") (pin "4") (pinfunction "IP-_4") (pintype "input"))
    )
    (net (code "28") (name "/PWR_ADC2CH13_PA05") (class "Default")
      (node (ref "R18") (pin "2") (pinfunction "2_2") (pintype "input"))
      (node (ref "U5") (pin "13") (pinfunction "PA5_13") (pintype "unspecified"))
    )
    (net (code "29") (name "/RPM_ADC2CH04_PA07") (class "Default")
      (node (ref "R19") (pin "2") (pinfunction "2_2") (pintype "input"))
      (node (ref "U5") (pin "15") (pinfunction "PA7_15") (pintype "unspecified"))
    )
    (net (code "30") (name "/RPM_SIG") (class "Default")
      (node (ref "CN2") (pin "2") (pinfunction "2_2") (pintype "unspecified"))
      (node (ref "R17") (pin "2") (pinfunction "2_2") (pintype "input"))
    )
    (net (code "31") (name "/SWCLK") (class "Default")
      (node (ref "H1") (pin "5") (pinfunction "5_5") (pintype "unspecified"))
      (node (ref "U5") (pin "38") (pinfunction "PA14_38") (pintype "unspecified"))
    )
    (net (code "32") (name "/SWDIO") (class "Default")
      (node (ref "H1") (pin "6") (pinfunction "6_6") (pintype "unspecified"))
      (node (ref "U5") (pin "37") (pinfunction "PA13_37") (pintype "unspecified"))
    )
    (net (code "33") (name "3V3") (class "Default")
      (node (ref "C11") (pin "2") (pinfunction "2_2") (pintype "unspecified"))
      (node (ref "C12") (pin "2") (pinfunction "2_2") (pintype "input"))
      (node (ref "C25") (pin "1") (pinfunction "1_1") (pintype "unspecified"))
      (node (ref "C26") (pin "1") (pinfunction "1_1") (pintype "unspecified"))
      (node (ref "C27") (pin "1") (pinfunction "1_1") (pintype "unspecified"))
      (node (ref "C28") (pin "1") (pinfunction "1_1") (pintype "unspecified"))
      (node (ref "C29") (pin "1") (pinfunction "1_1") (pintype "unspecified"))
      (node (ref "C31") (pin "1") (pinfunction "1_1") (pintype "unspecified"))
      (node (ref "C32") (pin "1") (pinfunction "1_1") (pintype "unspecified"))
      (node (ref "C33") (pin "2") (pinfunction "2_2") (pintype "unspecified"))
      (node (ref "H1") (pin "7") (pinfunction "7_7") (pintype "unspecified"))
      (node (ref "R25") (pin "2") (pinfunction "2_2") (pintype "input"))
      (node (ref "R28") (pin "2") (pinfunction "2_2") (pintype "input"))
      (node (ref "R29") (pin "2") (pinfunction "2_2") (pintype "input"))
      (node (ref "R30") (pin "2") (pinfunction "2_2") (pintype "input"))
      (node (ref "R8") (pin "1") (pinfunction "1_1") (pintype "input"))
      (node (ref "U4") (pin "2") (pinfunction "OUT_2") (pintype "unspecified"))
      (node (ref "U5") (pin "1") (pinfunction "VBAT_1") (pintype "unspecified"))
      (node (ref "U5") (pin "20") (pinfunction "VREF+_20") (pintype "unspecified"))
      (node (ref "U5") (pin "21") (pinfunction "VDDA_21") (pintype "unspecified"))
      (node (ref "U5") (pin "24") (pinfunction "VDD_24") (pintype "unspecified"))
      (node (ref "U5") (pin "36") (pinfunction "VDD_36") (pintype "unspecified"))
      (node (ref "U5") (pin "48") (pinfunction "VDD_48") (pintype "unspecified"))
    )
    (net (code "34") (name "12V") (class "Default")
      (node (ref "C3") (pin "2") (pinfunction "2_2") (pintype "unspecified"))
      (node (ref "C4") (pin "1") (pinfunction "1_1") (pintype "input"))
      (node (ref "D1") (pin "1") (pinfunction "A_1") (pintype "unspecified"))
      (node (ref "D2") (pin "1") (pinfunction "A_1") (pintype "unspecified"))
      (node (ref "D3") (pin "1") (pinfunction "A_1") (pintype "unspecified"))
      (node (ref "LDO1") (pin "1") (pinfunction "IN_1") (pintype "unspecified"))
      (node (ref "R2") (pin "1") (pinfunction "1_1") (pintype "input"))
      (node (ref "U2") (pin "3") (pinfunction "VOUT_3") (pintype "unspecified"))
      (node (ref "U4") (pin "3") (pinfunction "IN_3") (pintype "unspecified"))
    )
    (net (code "35") (name "AGND") (class "Default")
      (node (ref "C5") (pin "1") (pinfunction "1_1") (pintype "unspecified"))
      (node (ref "C6") (pin "1") (pinfunction "1_1") (pintype "unspecified"))
      (node (ref "CN1") (pin "11") (pinfunction "11_11") (pintype "unspecified"))
      (node (ref "CN2") (pin "3") (pinfunction "3_3") (pintype "unspecified"))
      (node (ref "L2") (pin "1") (pinfunction "1_1") (pintype "input"))
      (node (ref "R4") (pin "2") (pinfunction "2_2") (pintype "input"))
      (node (ref "U1") (pin "5") (pinfunction "GND_5") (pintype "input"))
    )
    (net (code "36") (name "GND") (class "Default")
      (node (ref "C11") (pin "1") (pinfunction "1_1") (pintype "unspecified"))
      (node (ref "C12") (pin "1") (pinfunction "1_1") (pintype "input"))
      (node (ref "C23") (pin "1") (pinfunction "1_1") (pintype "unspecified"))
      (node (ref "C24") (pin "1") (pinfunction "1_1") (pintype "unspecified"))
      (node (ref "C25") (pin "2") (pinfunction "2_2") (pintype "unspecified"))
      (node (ref "C26") (pin "2") (pinfunction "2_2") (pintype "unspecified"))
      (node (ref "C27") (pin "2") (pinfunction "2_2") (pintype "unspecified"))
      (node (ref "C28") (pin "2") (pinfunction "2_2") (pintype "unspecified"))
      (node (ref "C29") (pin "2") (pinfunction "2_2") (pintype "unspecified"))
      (node (ref "C3") (pin "1") (pinfunction "1_1") (pintype "unspecified"))
      (node (ref "C31") (pin "2") (pinfunction "2_2") (pintype "unspecified"))
      (node (ref "C32") (pin "2") (pinfunction "2_2") (pintype "unspecified"))
      (node (ref "C33") (pin "1") (pinfunction "1_1") (pintype "unspecified"))
      (node (ref "C4") (pin "2") (pinfunction "2_2") (pintype "input"))
      (node (ref "C7") (pin "1") (pinfunction "1_1") (pintype "unspecified"))
      (node (ref "C8") (pin "1") (pinfunction "1_1") (pintype "input"))
      (node (ref "H1") (pin "8") (pinfunction "8_8") (pintype "unspecified"))
      (node (ref "L1") (pin "2") (pinfunction "2_2") (pintype "input"))
      (node (ref "L2") (pin "2") (pinfunction "2_2") (pintype "input"))
      (node (ref "LDO1") (pin "2") (pinfunction "GND_2") (pintype "unspecified"))
      (node (ref "LED1") (pin "1") (pinfunction "K_1") (pintype "unspecified"))
      (node (ref "LED2") (pin "1") (pinfunction "K_1") (pintype "unspecified"))
      (node (ref "LED3") (pin "1") (pinfunction "K_1") (pintype "unspecified"))
      (node (ref "R20") (pin "1") (pinfunction "1_1") (pintype "input"))
      (node (ref "R21") (pin "1") (pinfunction "1_1") (pintype "input"))
      (node (ref "R27") (pin "1") (pinfunction "1_1") (pintype "input"))
      (node (ref "U3") (pin "8") (pinfunction "GND_8") (pintype "unspecified"))
      (node (ref "U4") (pin "1") (pinfunction "GND_1") (pintype "unspecified"))
      (node (ref "U5") (pin "19") (pinfunction "VSSA_19") (pintype "unspecified"))
      (node (ref "U5") (pin "23") (pinfunction "VSS_23") (pintype "unspecified"))
      (node (ref "U5") (pin "35") (pinfunction "VSS_35") (pintype "unspecified"))
      (node (ref "U5") (pin "47") (pinfunction "VSS_47") (pintype "unspecified"))
    )
    (net (code "37") (name "Net-(D1-K)") (class "Default")
      (node (ref "C9") (pin "2") (pinfunction "2_2") (pintype "input"))
      (node (ref "D1") (pin "2") (pinfunction "K_2") (pintype "unspecified"))
      (node (ref "U3") (pin "20") (pinfunction "VB1_20") (pintype "unspecified"))
    )
    (net (code "38") (name "Net-(D2-K)") (class "Default")
      (node (ref "C10") (pin "2") (pinfunction "2_2") (pintype "input"))
      (node (ref "D2") (pin "2") (pinfunction "K_2") (pintype "unspecified"))
      (node (ref "U3") (pin "17") (pinfunction "VB2_17") (pintype "unspecified"))
    )
    (net (code "39") (name "Net-(D3-K)") (class "Default")
      (node (ref "C13") (pin "2") (pinfunction "2_2") (pintype "input"))
      (node (ref "D3") (pin "2") (pinfunction "K_2") (pintype "unspecified"))
      (node (ref "U3") (pin "14") (pinfunction "VB3_14") (pintype "unspecified"))
    )
    (net (code "40") (name "Net-(LED1-A)") (class "Default")
      (node (ref "LED1") (pin "2") (pinfunction "A_2") (pintype "unspecified"))
      (node (ref "R2") (pin "2") (pinfunction "2_2") (pintype "input"))
    )
    (net (code "41") (name "Net-(LED2-A)") (class "Default")
      (node (ref "LED2") (pin "2") (pinfunction "A_2") (pintype "unspecified"))
      (node (ref "R7") (pin "2") (pinfunction "2_2") (pintype "input"))
    )
    (net (code "42") (name "Net-(LED3-A)") (class "Default")
      (node (ref "LED3") (pin "2") (pinfunction "A_2") (pintype "unspecified"))
      (node (ref "R8") (pin "2") (pinfunction "2_2") (pintype "input"))
    )
    (net (code "43") (name "Net-(LED4-A)") (class "Default")
      (node (ref "LED4") (pin "2") (pinfunction "A_2") (pintype "unspecified"))
      (node (ref "R28") (pin "1") (pinfunction "1_1") (pintype "input"))
    )
    (net (code "44") (name "Net-(LED4-K)") (class "Default")
      (node (ref "LED4") (pin "1") (pinfunction "K_1") (pintype "unspecified"))
      (node (ref "U5") (pin "4") (pinfunction "PC15-OSC32_OUT_4") (pintype "unspecified"))
    )
    (net (code "45") (name "Net-(LED5-A)") (class "Default")
      (node (ref "LED5") (pin "2") (pinfunction "A_2") (pintype "unspecified"))
      (node (ref "R29") (pin "1") (pinfunction "1_1") (pintype "input"))
    )
    (net (code "46") (name "Net-(LED5-K)") (class "Default")
      (node (ref "LED5") (pin "1") (pinfunction "K_1") (pintype "unspecified"))
      (node (ref "U5") (pin "3") (pinfunction "PC14-OSC32_IN_3") (pintype "unspecified"))
    )
    (net (code "47") (name "Net-(LED6-A)") (class "Default")
      (node (ref "LED6") (pin "2") (pinfunction "A_2") (pintype "unspecified"))
      (node (ref "R30") (pin "1") (pinfunction "1_1") (pintype "input"))
    )
    (net (code "48") (name "Net-(LED6-K)") (class "Default")
      (node (ref "LED6") (pin "1") (pinfunction "K_1") (pintype "unspecified"))
      (node (ref "U5") (pin "2") (pinfunction "PC13_2") (pintype "unspecified"))
    )
    (net (code "49") (name "Net-(Q1-G)") (class "Default")
      (node (ref "Q1") (pin "1") (pinfunction "G_1") (pintype "unspecified"))
      (node (ref "R10") (pin "1") (pinfunction "1_1") (pintype "input"))
    )
    (net (code "50") (name "Net-(Q2-G)") (class "Default")
      (node (ref "Q2") (pin "1") (pinfunction "G_1") (pintype "unspecified"))
      (node (ref "R11") (pin "1") (pinfunction "1_1") (pintype "input"))
    )
    (net (code "51") (name "Net-(Q3-G)") (class "Default")
      (node (ref "Q3") (pin "1") (pinfunction "G_1") (pintype "unspecified"))
      (node (ref "R12") (pin "1") (pinfunction "1_1") (pintype "input"))
    )
    (net (code "52") (name "Net-(Q4-G)") (class "Default")
      (node (ref "Q4") (pin "1") (pinfunction "G_1") (pintype "unspecified"))
      (node (ref "R22") (pin "1") (pinfunction "1_1") (pintype "input"))
    )
    (net (code "53") (name "Net-(Q5-G)") (class "Default")
      (node (ref "Q5") (pin "1") (pinfunction "G_1") (pintype "unspecified"))
      (node (ref "R23") (pin "1") (pinfunction "1_1") (pintype "input"))
    )
    (net (code "54") (name "Net-(Q6-G)") (class "Default")
      (node (ref "Q6") (pin "1") (pinfunction "G_1") (pintype "unspecified"))
      (node (ref "R24") (pin "1") (pinfunction "1_1") (pintype "input"))
    )
    (net (code "55") (name "Net-(R16-Pad1)") (class "Default")
      (node (ref "R16") (pin "1") (pinfunction "1_1") (pintype "input"))
      (node (ref "R18") (pin "1") (pinfunction "1_1") (pintype "input"))
      (node (ref "R20") (pin "2") (pinfunction "2_2") (pintype "input"))
    )
    (net (code "56") (name "Net-(R17-Pad1)") (class "Default")
      (node (ref "R17") (pin "1") (pinfunction "1_1") (pintype "input"))
      (node (ref "R19") (pin "1") (pinfunction "1_1") (pintype "input"))
      (node (ref "R21") (pin "2") (pinfunction "2_2") (pintype "input"))
    )
    (net (code "57") (name "Net-(U1-OUT)") (class "Default")
      (node (ref "R1") (pin "2") (pinfunction "2_2") (pintype "input"))
      (node (ref "U1") (pin "7") (pinfunction "OUT_7") (pintype "input"))
    )
    (net (code "58") (name "PGND") (class "Default")
      (node (ref "C1") (pin "2") (pinfunction "2_2") (pintype "input"))
      (node (ref "C14") (pin "2") (pinfunction "2_2") (pintype "input"))
      (node (ref "C15") (pin "2") (pinfunction "2_2") (pintype "input"))
      (node (ref "C16") (pin "2") (pinfunction "2_2") (pintype "input"))
      (node (ref "C2") (pin "1") (pinfunction "1_1") (pintype "unspecified"))
      (node (ref "CN1") (pin "2") (pinfunction "2_2") (pintype "unspecified"))
      (node (ref "CN1") (pin "4") (pinfunction "4_4") (pintype "unspecified"))
      (node (ref "D7") (pin "1") (pinfunction "A_1") (pintype "unspecified"))
      (node (ref "D8") (pin "1") (pinfunction "A_1") (pintype "unspecified"))
      (node (ref "D9") (pin "1") (pinfunction "A_1") (pintype "unspecified"))
      (node (ref "L1") (pin "1") (pinfunction "1_1") (pintype "input"))
      (node (ref "Q4") (pin "3") (pinfunction "S_3") (pintype "unspecified"))
      (node (ref "Q5") (pin "3") (pinfunction "S_3") (pintype "unspecified"))
      (node (ref "Q6") (pin "3") (pinfunction "S_3") (pintype "unspecified"))
      (node (ref "U2") (pin "2") (pinfunction "GND_2") (pintype "unspecified"))
    )
    (net (code "59") (name "POWER") (class "Default")
      (node (ref "C1") (pin "1") (pinfunction "1_1") (pintype "input"))
      (node (ref "C2") (pin "2") (pinfunction "2_2") (pintype "unspecified"))
      (node (ref "CN1") (pin "1") (pinfunction "1_1") (pintype "unspecified"))
      (node (ref "CN1") (pin "3") (pinfunction "3_3") (pintype "unspecified"))
      (node (ref "R16") (pin "2") (pinfunction "2_2") (pintype "input"))
      (node (ref "U1") (pin "1") (pinfunction "IP+_1") (pintype "input"))
      (node (ref "U1") (pin "2") (pinfunction "IP+_2") (pintype "input"))
      (node (ref "U2") (pin "1") (pinfunction "VCC_1") (pintype "unspecified"))
    )
    (net (code "60") (name "unconnected-(U1-VZCR-Pad6)") (class "Default")
      (node (ref "U1") (pin "6") (pinfunction "VZCR_6") (pintype "input+no_connect"))
    )
    (net (code "61") (name "unconnected-(U5-PA3-Pad11)") (class "Default")
      (node (ref "U5") (pin "11") (pinfunction "PA3_11") (pintype "unspecified+no_connect"))
    )
    (net (code "62") (name "unconnected-(U5-PA4-Pad12)") (class "Default")
      (node (ref "U5") (pin "12") (pinfunction "PA4_12") (pintype "unspecified+no_connect"))
    )
    (net (code "63") (name "unconnected-(U5-PA11-Pad33)") (class "Default")
      (node (ref "U5") (pin "33") (pinfunction "PA11_33") (pintype "unspecified+no_connect"))
    )
    (net (code "64") (name "unconnected-(U5-PA12-Pad34)") (class "Default")
      (node (ref "U5") (pin "34") (pinfunction "PA12_34") (pintype "unspecified+no_connect"))
    )
    (net (code "65") (name "unconnected-(U5-PA15-Pad39)") (class "Default")
      (node (ref "U5") (pin "39") (pinfunction "PA15_39") (pintype "unspecified+no_connect"))
    )
    (net (code "66") (name "unconnected-(U5-PB0-Pad16)") (class "Default")
      (node (ref "U5") (pin "16") (pinfunction "PB0_16") (pintype "unspecified+no_connect"))
    )
    (net (code "67") (name "unconnected-(U5-PB1-Pad17)") (class "Default")
      (node (ref "U5") (pin "17") (pinfunction "PB1_17") (pintype "unspecified+no_connect"))
    )
    (net (code "68") (name "unconnected-(U5-PB2-Pad18)") (class "Default")
      (node (ref "U5") (pin "18") (pinfunction "PB2_18") (pintype "unspecified+no_connect"))
    )
    (net (code "69") (name "unconnected-(U5-PB3-Pad40)") (class "Default")
      (node (ref "U5") (pin "40") (pinfunction "PB3_40") (pintype "unspecified+no_connect"))
    )
    (net (code "70") (name "unconnected-(U5-PB4-Pad41)") (class "Default")
      (node (ref "U5") (pin "41") (pinfunction "PB4_41") (pintype "unspecified+no_connect"))
    )
    (net (code "71") (name "unconnected-(U5-PB5-Pad42)") (class "Default")
      (node (ref "U5") (pin "42") (pinfunction "PB5_42") (pintype "unspecified+no_connect"))
    )
    (net (code "72") (name "unconnected-(U5-PB9-Pad46)") (class "Default")
      (node (ref "U5") (pin "46") (pinfunction "PB9_46") (pintype "unspecified+no_connect"))
    )
    (net (code "73") (name "unconnected-(U5-PB10-Pad22)") (class "Default")
      (node (ref "U5") (pin "22") (pinfunction "PB10_22") (pintype "unspecified+no_connect"))
    )
    (net (code "74") (name "unconnected-(U5-PB11-Pad25)") (class "Default")
      (node (ref "U5") (pin "25") (pinfunction "PB11_25") (pintype "unspecified+no_connect"))
    )
    (net (code "75") (name "unconnected-(U5-PB12-Pad26)") (class "Default")
      (node (ref "U5") (pin "26") (pinfunction "PB12_26") (pintype "unspecified+no_connect"))
    )
  )
)
